# amc7135-24mm-RGBW-led-driver-with-butt-m.net
KiCad netlist of a schematic drawn in EAGLE
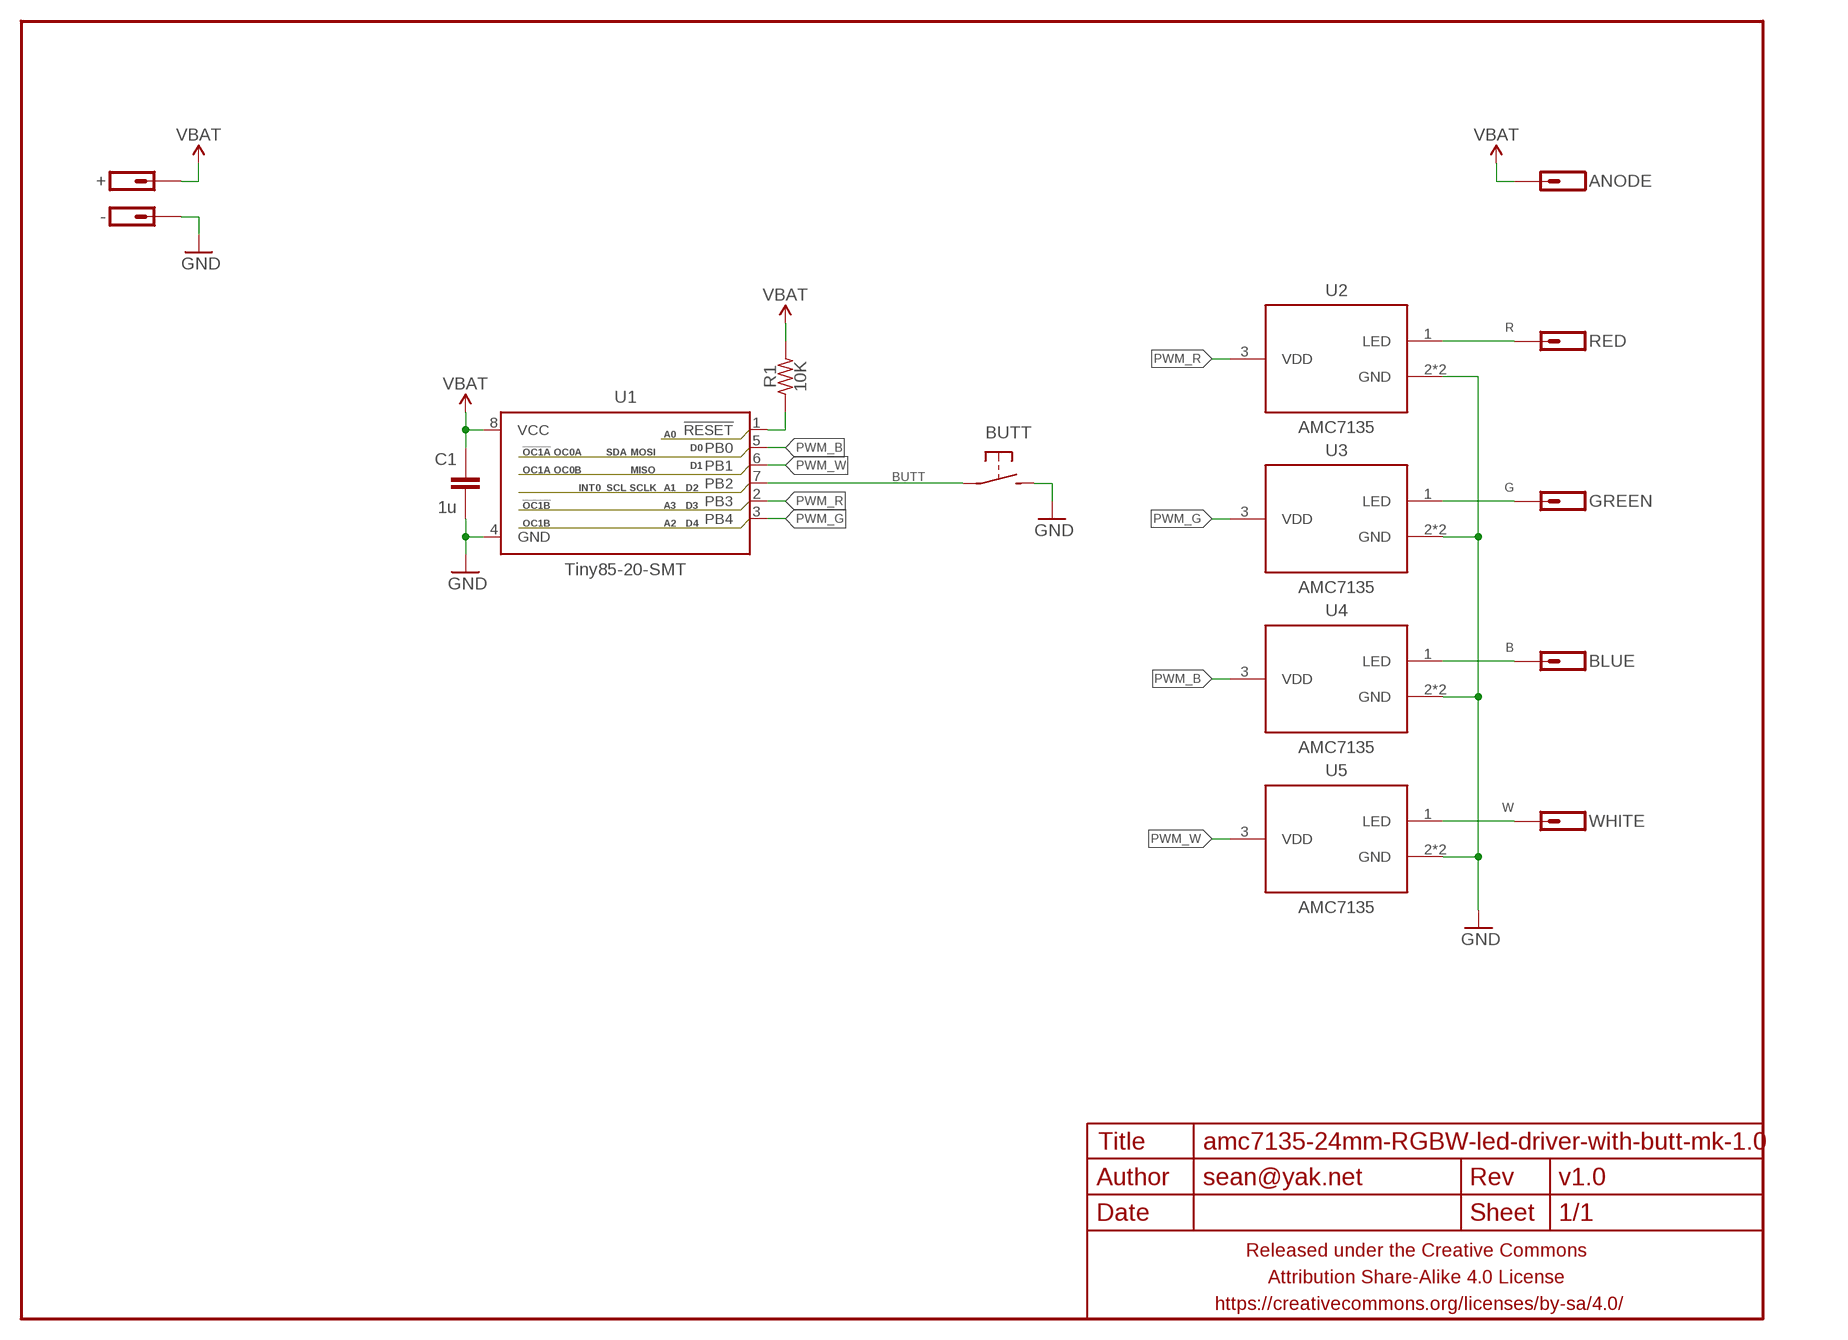
[diagram p0: schematic, sheet 1]

(export (version "E")
  (design (tool "Eeschema 10.0.6"))
  (components
    (comp (ref "+")
      (value "M01NOSTOP-CANTSTOP-DONTKNOWHOWTOSTOP")
      (footprint "eagle-import:1X01_SMD_NOSTOP_NOSILK")
      (libsource (lib "eagle-import") (part "M01NOSTOP-CANTSTOP-DONTKNOWHOWTOSTOP"))
    )
    (comp (ref "-")
      (value "M01NOT-A-VIA-NOPE")
      (footprint "eagle-import:1X01_NOSILK_NOSTOP")
      (libsource (lib "eagle-import") (part "M01NOT-A-VIA-NOPE"))
    )
    (comp (ref "ANODE")
      (value "M01PTH-1.2MM-NS")
      (footprint "eagle-import:1X01-1.2MM-NS")
      (libsource (lib "eagle-import") (part "M01PTH-1.2MM-NS"))
    )
    (comp (ref "BLUE")
      (value "M01PTH-1MM-CIR-NS")
      (footprint "eagle-import:1X01-1MM-CIR-NS")
      (libsource (lib "eagle-import") (part "M01PTH-1MM-CIR-NS"))
    )
    (comp (ref "BUTT")
      (value "SPST-NO-TACT3MM-RA")
      (footprint "eagle-import:TACTILE-PTH-SIDE")
      (libsource (lib "eagle-import") (part "SPST-NO-TACT3MM-RA"))
    )
    (comp (ref "C1")
      (value "1u")
      (footprint "eagle-import:C0402")
      (libsource (lib "eagle-import") (part "CAPACITOR-CERAMICC0402"))
    )
    (comp (ref "FRAME1")
      (value "FRAME-LETTERNO_PACKAGE")
      (footprint "eagle-import:DUMMY")
      (fields (field (name "DESIGNER") "sean@yak.net") (field (name "VERSION") "v1.0"))
      (libsource (lib "eagle-import") (part "FRAME-LETTERNO_PACKAGE"))
    )
    (comp (ref "GREEN")
      (value "M01PTH-1MM-CIR-NS")
      (footprint "eagle-import:1X01-1MM-CIR-NS")
      (libsource (lib "eagle-import") (part "M01PTH-1MM-CIR-NS"))
    )
    (comp (ref "R1")
      (value "10K")
      (footprint "eagle-import:R0402")
      (libsource (lib "eagle-import") (part "RESISTORR0402"))
    )
    (comp (ref "RED")
      (value "M01PTH-1MM-CIR-NS")
      (footprint "eagle-import:1X01-1MM-CIR-NS")
      (libsource (lib "eagle-import") (part "M01PTH-1MM-CIR-NS"))
    )
    (comp (ref "U1")
      (value "Tiny85-20-SMT")
      (footprint "eagle-import:SO08-EIAJ")
      (libsource (lib "eagle-import") (part "ATTINY45TINY85-20-SOICW"))
    )
    (comp (ref "U2")
      (value "AMC7135")
      (footprint "eagle-import:SOT89")
      (libsource (lib "eagle-import") (part "AMC7135SOT-89"))
    )
    (comp (ref "U3")
      (value "AMC7135")
      (footprint "eagle-import:SOT89")
      (libsource (lib "eagle-import") (part "AMC7135SOT-89"))
    )
    (comp (ref "U4")
      (value "AMC7135")
      (footprint "eagle-import:SOT89")
      (libsource (lib "eagle-import") (part "AMC7135SOT-89"))
    )
    (comp (ref "U5")
      (value "AMC7135")
      (footprint "eagle-import:SOT89")
      (libsource (lib "eagle-import") (part "AMC7135SOT-89"))
    )
    (comp (ref "WHITE")
      (value "M01PTH-1MM-CIR-NS")
      (footprint "eagle-import:1X01-1MM-CIR-NS")
      (libsource (lib "eagle-import") (part "M01PTH-1MM-CIR-NS"))
    )
  )
  (nets
    (net (code "1") (name "/B") (class "Default")
      (node (ref "BLUE") (pin "1") (pinfunction "1_1") (pintype "passive"))
      (node (ref "U4") (pin "1") (pinfunction "LED_1") (pintype "bidirectional"))
    )
    (net (code "2") (name "/BUTT") (class "Default")
      (node (ref "BUTT") (pin "1") (pinfunction "1_1") (pintype "passive"))
      (node (ref "U1") (pin "7") (pinfunction "PB2_7") (pintype "bidirectional"))
    )
    (net (code "3") (name "/G") (class "Default")
      (node (ref "GREEN") (pin "1") (pinfunction "1_1") (pintype "passive"))
      (node (ref "U3") (pin "1") (pinfunction "LED_1") (pintype "bidirectional"))
    )
    (net (code "4") (name "/R") (class "Default")
      (node (ref "RED") (pin "1") (pinfunction "1_1") (pintype "passive"))
      (node (ref "U2") (pin "1") (pinfunction "LED_1") (pintype "bidirectional"))
    )
    (net (code "5") (name "/W") (class "Default")
      (node (ref "U5") (pin "1") (pinfunction "LED_1") (pintype "bidirectional"))
      (node (ref "WHITE") (pin "1") (pinfunction "1_1") (pintype "passive"))
    )
    (net (code "6") (name "GND") (class "Default")
      (node (ref "-") (pin "P$1") (pinfunction "1_P$1") (pintype "passive"))
      (node (ref "BUTT") (pin "2") (pinfunction "2_2") (pintype "passive"))
      (node (ref "C1") (pin "2") (pinfunction "2_2") (pintype "passive"))
      (node (ref "U1") (pin "4") (pinfunction "GND_4") (pintype "bidirectional"))
      (node (ref "U2") (pin "2") (pinfunction "GND_2") (pintype "bidirectional"))
      (node (ref "U2") (pin "4") (pinfunction "GND_4") (pintype "bidirectional"))
      (node (ref "U3") (pin "2") (pinfunction "GND_2") (pintype "bidirectional"))
      (node (ref "U3") (pin "4") (pinfunction "GND_4") (pintype "bidirectional"))
      (node (ref "U4") (pin "2") (pinfunction "GND_2") (pintype "bidirectional"))
      (node (ref "U4") (pin "4") (pinfunction "GND_4") (pintype "bidirectional"))
      (node (ref "U5") (pin "2") (pinfunction "GND_2") (pintype "bidirectional"))
      (node (ref "U5") (pin "4") (pinfunction "GND_4") (pintype "bidirectional"))
    )
    (net (code "7") (name "Net-(U1-~{RESET})") (class "Default")
      (node (ref "R1") (pin "1") (pinfunction "1_1") (pintype "passive"))
      (node (ref "U1") (pin "1") (pinfunction "~{RESET}_1") (pintype "bidirectional"))
    )
    (net (code "8") (name "PWM_B") (class "Default")
      (node (ref "U1") (pin "5") (pinfunction "PB0_5") (pintype "bidirectional"))
      (node (ref "U4") (pin "3") (pinfunction "VDD_3") (pintype "bidirectional"))
    )
    (net (code "9") (name "PWM_G") (class "Default")
      (node (ref "U1") (pin "3") (pinfunction "PB4_3") (pintype "bidirectional"))
      (node (ref "U3") (pin "3") (pinfunction "VDD_3") (pintype "bidirectional"))
    )
    (net (code "10") (name "PWM_R") (class "Default")
      (node (ref "U1") (pin "2") (pinfunction "PB3_2") (pintype "bidirectional"))
      (node (ref "U2") (pin "3") (pinfunction "VDD_3") (pintype "bidirectional"))
    )
    (net (code "11") (name "PWM_W") (class "Default")
      (node (ref "U1") (pin "6") (pinfunction "PB1_6") (pintype "bidirectional"))
      (node (ref "U5") (pin "3") (pinfunction "VDD_3") (pintype "bidirectional"))
    )
    (net (code "12") (name "VBAT") (class "Default")
      (node (ref "+") (pin "1") (pinfunction "1_1") (pintype "passive"))
      (node (ref "ANODE") (pin "P$1") (pinfunction "1_P$1") (pintype "passive"))
      (node (ref "C1") (pin "1") (pinfunction "1_1") (pintype "passive"))
      (node (ref "R1") (pin "2") (pinfunction "2_2") (pintype "passive"))
      (node (ref "U1") (pin "8") (pinfunction "VCC_8") (pintype "bidirectional"))
    )
  )
)
